# STM32_Peripherals.net
KiCad netlist of a schematic drawn in Altium Designer
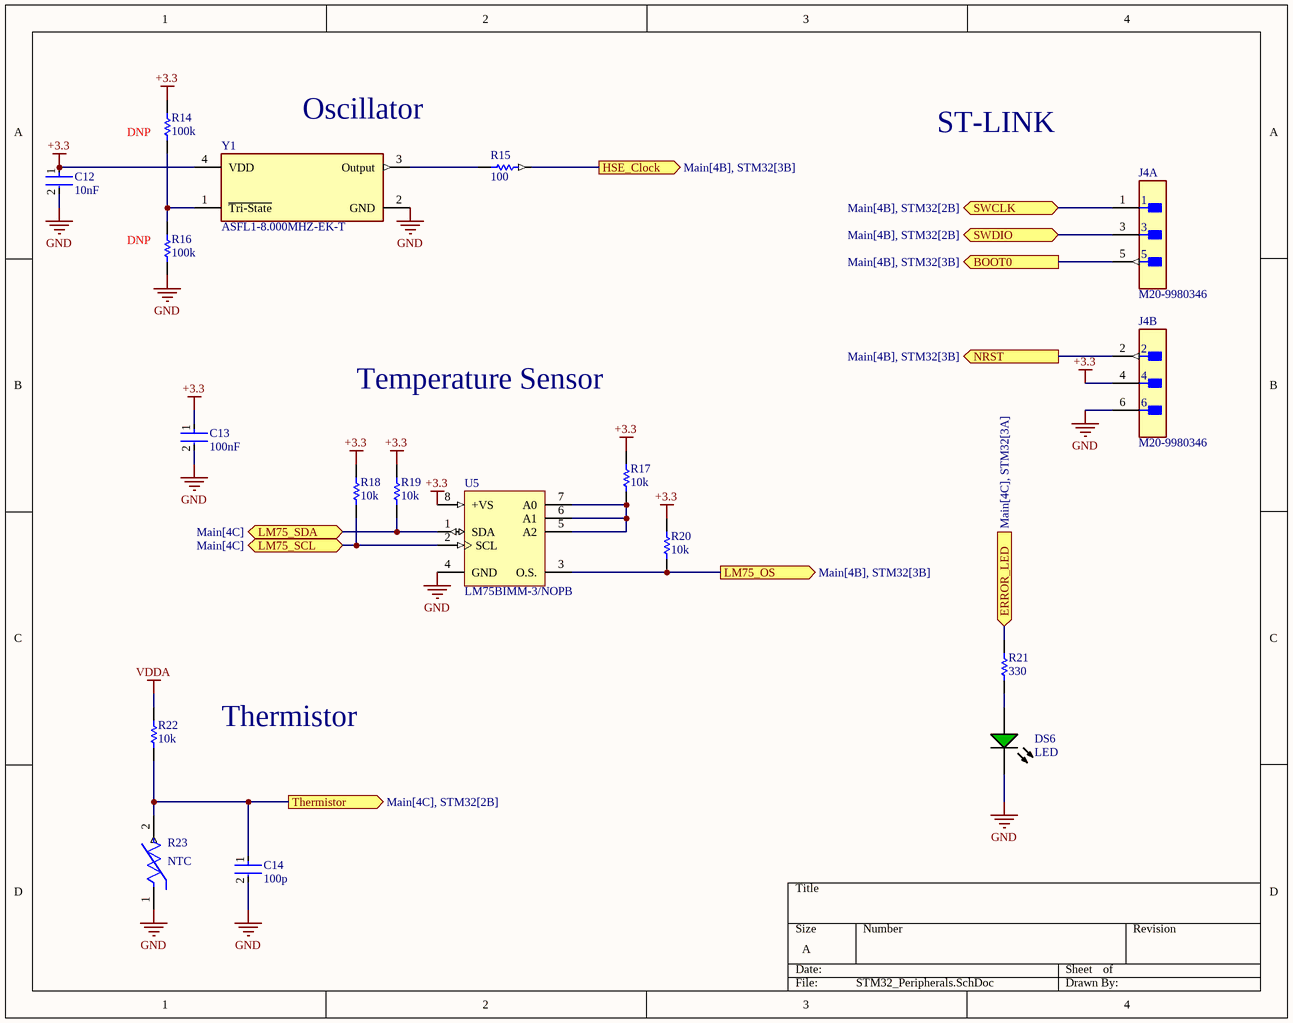
[diagram p0: STM32_Peripherals.SchDoc]

(export (version "E")
  (design (tool "Eeschema 10.0.6"))
  (components
    (comp (ref "C12")
      (value "10nF")
      (footprint "FP-0805-L_2_01_0_2-W_1_25-IPC_B")
      (description "General Purpose Ceramic Capacitor, 0805, 10nF, 10%, X7R, 15%, 100V")
      (fields (field (name "VOLTAGE") "100V") (field (name "TOLERANCE") "10%"))
      (libsource (lib "Altium Content Vault") (part "b4654b650e69147ec39a6b967a45e02"))
    )
    (comp (ref "C13")
      (value "100nF")
      (footprint "FP-0805-L_2_01_0_2-W_1_25-IPC_B")
      (description "General Purpose Ceramic Capacitor, 0805, 100nF, 10%, X7R, 15%, 100V")
      (fields (field (name "VOLTAGE") "100V") (field (name "TOLERANCE") "10%"))
      (libsource (lib "Altium Content Vault") (part "b4654b650e69147ec39a6b967a45e02"))
    )
    (comp (ref "C14")
      (value "100p")
      (footprint "FP-0805-L_2_01_0_2-W_1_25-IPC_B")
      (description "General Purpose Ceramic Capacitor, 0805, 100pF, 10%, X7R, 15%, 100V")
      (fields (field (name "VOLTAGE") "100V") (field (name "TOLERANCE") "10%"))
      (libsource (lib "Altium Content Vault") (part "b4654b650e69147ec39a6b967a45e02"))
    )
    (comp (ref "DS6")
      (value "LED")
      (footprint "AVAG-HSMX-C170_V")
      (description "Chip LED, Green, 2.2 V, -40 to 85 degC, 2-Pin SMD, Pb-Free, Tape and Reel")
      (fields (field (name "MANUFACTURER") "Avago"))
      (libsource (lib "Altium Content Vault") (part "LED_GREEN_A1K2-2"))
    )
    (comp (ref "J4")
      (value "M20-9980346")
      (footprint "FP-M20-9980346-MFG")
      (description "CONN HEADER VERT 6POS 2.54MM")
      (fields
        (field (name "MANUFACTURER") "Harwin")
        (field (name "OCTOPART") "https://octopart.com/m20-9980346-harwin-5436545")
      )
      (libsource (lib "Altium Content Vault") (part "2654a11fb13586ecb194516b1c997bc"))
    )
    (comp (ref "R14")
      (value "100k")
      (footprint "RESC2013X50X30LL20T20")
      (fields (field (name "MANUFACTURER") "Vishay Dale") (field (name "PART NUMBER") "CRCW08050000Z0EA"))
      (libsource (lib "Altium Content Vault") (part "RES"))
    )
    (comp (ref "R15")
      (value "100")
      (footprint "RESC2013X50X30LL20T20")
      (fields (field (name "MANUFACTURER") "Vishay Dale") (field (name "PART NUMBER") "CRCW08050000Z0EA"))
      (libsource (lib "") (part "RES_1"))
    )
    (comp (ref "R16")
      (value "100k")
      (footprint "RESC2013X50X30LL20T20")
      (fields (field (name "MANUFACTURER") "Vishay Dale") (field (name "PART NUMBER") "CRCW08050000Z0EA"))
      (libsource (lib "Altium Content Vault") (part "RES"))
    )
    (comp (ref "R17")
      (value "10k")
      (footprint "RESC2013X50X30LL20T20")
      (fields (field (name "MANUFACTURER") "Vishay Dale") (field (name "PART NUMBER") "CRCW08050000Z0EA"))
      (libsource (lib "Altium Content Vault") (part "RES"))
    )
    (comp (ref "R18")
      (value "10k")
      (footprint "RESC2013X50X30LL20T20")
      (fields (field (name "MANUFACTURER") "Vishay Dale") (field (name "PART NUMBER") "CRCW08050000Z0EA"))
      (libsource (lib "Altium Content Vault") (part "RES"))
    )
    (comp (ref "R19")
      (value "10k")
      (footprint "RESC2013X50X30LL20T20")
      (fields (field (name "MANUFACTURER") "Vishay Dale") (field (name "PART NUMBER") "CRCW08050000Z0EA"))
      (libsource (lib "Altium Content Vault") (part "RES"))
    )
    (comp (ref "R20")
      (value "10k")
      (footprint "RESC2013X50X30LL20T20")
      (fields (field (name "MANUFACTURER") "Vishay Dale") (field (name "PART NUMBER") "CRCW08050000Z0EA"))
      (libsource (lib "Altium Content Vault") (part "RES"))
    )
    (comp (ref "R21")
      (value "330")
      (footprint "RESC2013X50X30LL20T20")
      (fields (field (name "MANUFACTURER") "Vishay Dale") (field (name "PART NUMBER") "CRCW08050000Z0EA"))
      (libsource (lib "Altium Content Vault") (part "RES"))
    )
    (comp (ref "R22")
      (value "10k")
      (footprint "RESC2013X50X30LL20T20")
      (fields (field (name "MANUFACTURER") "Vishay Dale") (field (name "PART NUMBER") "CRCW08050000Z0EA"))
      (libsource (lib "Altium Content Vault") (part "RES"))
    )
    (comp (ref "R23")
      (value "NTC")
      (footprint "FP-NTCALUG02A103G-MFG")
      (description "THERM NTC 10KOHM 3984K RING LUG")
      (fields (field (name "TOLERANCE") "2%"))
      (libsource (lib "Altium Content Vault") (part "3b148a6ebabc5fb4d708a66c052d352"))
    )
    (comp (ref "U5")
      (value "LM75BIMM-3/NOPB")
      (footprint "DGK0008A_L")
      (description "Digital Temperature Sensor and Thermal Watchdog with Two-Wire Interface, 8-pin Mini SOIC, Pb-Free")
      (fields (field (name "MANUFACTURER") "Texas Instruments"))
      (libsource (lib "Altium Content Vault") (part "SEN-TEMP-LM75BIM-8"))
    )
    (comp (ref "Y1")
      (value "ASFL1-8.000MHZ-EK-T")
      (footprint "FP-ASFL1-MFG")
      (description "XTAL Oscillator 8MHz ±30ppm HCMOS, TTL 3.3V 4-SMD 5mm x 3.2mm")
      (libsource (lib "Altium Content Vault") (part "47df00dc2349451232cb22fac08fbff"))
    )
  )
  (nets
    (net (code "1") (name "+3.3") (class "Default")
      (node (ref "C12") (pin "1") (pinfunction "1_1") (pintype "passive"))
      (node (ref "C13") (pin "1") (pinfunction "1_1") (pintype "passive"))
      (node (ref "J4") (pin "4") (pinfunction "4_4") (pintype "passive"))
      (node (ref "R14") (pin "2") (pinfunction "2_2") (pintype "passive"))
      (node (ref "R17") (pin "2") (pinfunction "2_2") (pintype "passive"))
      (node (ref "R18") (pin "2") (pinfunction "2_2") (pintype "passive"))
      (node (ref "R19") (pin "2") (pinfunction "2_2") (pintype "passive"))
      (node (ref "R20") (pin "2") (pinfunction "2_2") (pintype "passive"))
      (node (ref "U5") (pin "8") (pinfunction "+VS_8") (pintype "input"))
      (node (ref "Y1") (pin "4") (pinfunction "VDD_4") (pintype "power_in"))
    )
    (net (code "3") (name "/BOOT0") (class "Default")
      (node (ref "J4") (pin "5") (pinfunction "5_5") (pintype "passive"))
    )
    (net (code "4") (name "/ERROR_LED") (class "Default")
      (node (ref "R21") (pin "2") (pinfunction "2_2") (pintype "passive"))
    )
    (net (code "5") (name "/HSE_Clock") (class "Default")
      (node (ref "R15") (pin "2") (pinfunction "2_2") (pintype "output"))
    )
    (net (code "6") (name "/LM75_OS") (class "Default")
      (node (ref "R20") (pin "1") (pinfunction "1_1") (pintype "passive"))
      (node (ref "U5") (pin "3") (pinfunction "O.S._3") (pintype "open_collector"))
    )
    (net (code "7") (name "/LM75_SCL") (class "Default")
      (node (ref "R18") (pin "1") (pinfunction "1_1") (pintype "passive"))
      (node (ref "U5") (pin "2") (pinfunction "SCL_2") (pintype "input"))
    )
    (net (code "8") (name "/LM75_SDA") (class "Default")
      (node (ref "R19") (pin "1") (pinfunction "1_1") (pintype "passive"))
      (node (ref "U5") (pin "1") (pinfunction "SDA_1") (pintype "bidirectional"))
    )
    (net (code "9") (name "/NRST") (class "Default")
      (node (ref "J4") (pin "2") (pinfunction "2_2") (pintype "output"))
    )
    (net (code "10") (name "/SWCLK") (class "Default")
      (node (ref "J4") (pin "1") (pinfunction "1_1") (pintype "passive"))
    )
    (net (code "11") (name "/SWDIO") (class "Default")
      (node (ref "J4") (pin "3") (pinfunction "3_3") (pintype "passive"))
    )
    (net (code "12") (name "/Thermistor") (class "Default")
      (node (ref "C14") (pin "1") (pinfunction "1_1") (pintype "passive"))
      (node (ref "R22") (pin "1") (pinfunction "1_1") (pintype "passive"))
      (node (ref "R23") (pin "2") (pinfunction "2_2") (pintype "output"))
    )
    (net (code "13") (name "GND") (class "Default")
      (node (ref "C12") (pin "2") (pinfunction "2_2") (pintype "passive"))
      (node (ref "C13") (pin "2") (pinfunction "2_2") (pintype "passive"))
      (node (ref "C14") (pin "2") (pinfunction "2_2") (pintype "passive"))
      (node (ref "DS6") (pin "2") (pinfunction "K_2") (pintype "passive"))
      (node (ref "J4") (pin "6") (pinfunction "6_6") (pintype "passive"))
      (node (ref "R16") (pin "1") (pinfunction "1_1") (pintype "passive"))
      (node (ref "R23") (pin "1") (pinfunction "1_1") (pintype "passive"))
      (node (ref "U5") (pin "4") (pinfunction "GND_4") (pintype "power_in"))
      (node (ref "Y1") (pin "2") (pinfunction "GND_2") (pintype "power_in"))
    )
    (net (code "14") (name "Net-(DS6-A)") (class "Default")
      (node (ref "DS6") (pin "1") (pinfunction "A_1") (pintype "passive"))
      (node (ref "R21") (pin "1") (pinfunction "1_1") (pintype "passive"))
    )
    (net (code "15") (name "Net-(U5-A0)") (class "Default")
      (node (ref "R17") (pin "1") (pinfunction "1_1") (pintype "passive"))
      (node (ref "U5") (pin "5") (pinfunction "A2_5") (pintype "passive"))
      (node (ref "U5") (pin "6") (pinfunction "A1_6") (pintype "passive"))
      (node (ref "U5") (pin "7") (pinfunction "A0_7") (pintype "passive"))
    )
    (net (code "16") (name "Net-(Y1-Output)") (class "Default")
      (node (ref "R15") (pin "1") (pinfunction "1_1") (pintype "passive"))
      (node (ref "Y1") (pin "3") (pinfunction "Output_3") (pintype "output"))
    )
    (net (code "17") (name "Net-(Y1-~{Tri-State})") (class "Default")
      (node (ref "R14") (pin "1") (pinfunction "1_1") (pintype "passive"))
      (node (ref "R16") (pin "2") (pinfunction "2_2") (pintype "passive"))
      (node (ref "Y1") (pin "1") (pinfunction "~{Tri-State}_1") (pintype "passive"))
    )
    (net (code "18") (name "VDDA") (class "Default")
      (node (ref "R22") (pin "2") (pinfunction "2_2") (pintype "passive"))
    )
  )
)
